# OLED.net
KiCad netlist of a schematic drawn in Altium Designer
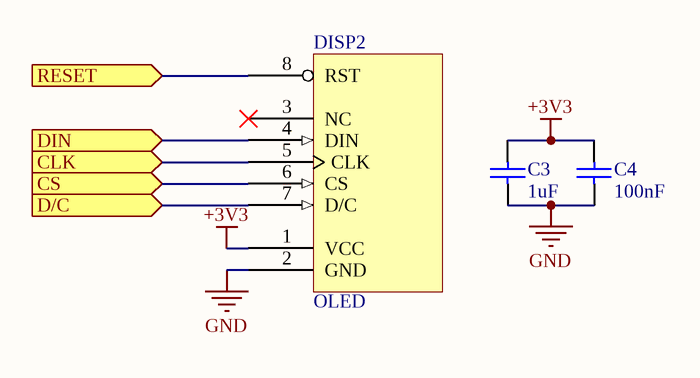
[diagram p0: OLED.SchDoc]

(export (version "E")
  (design (tool "Eeschema 10.0.6"))
  (components
    (comp (ref "C3")
      (value "1uF")
      (footprint "CAP_0805_IPC_MD")
      (description "Capacitor")
      (fields (field (name "MANUFACTURER") "Samsung") (field (name "Comment") "Cap"))
      (libsource (lib "DataLogger") (part "Cap"))
    )
    (comp (ref "C4")
      (value "100nF")
      (footprint "CAP_0805_IPC_MD")
      (description "Capacitor")
      (fields (field (name "MANUFACTURER") "Samsung") (field (name "Comment") "Cap"))
      (libsource (lib "DataLogger") (part "Cap"))
    )
    (comp (ref "DISP2")
      (value "OLED")
      (footprint "OLED_1.3_INCH")
      (libsource (lib "Dashboard") (part "OLED"))
    )
  )
  (nets
    (net (code "1") (name "+3V3") (class "Default")
      (node (ref "C3") (pin "2") (pinfunction "2_2") (pintype "passive"))
      (node (ref "C4") (pin "2") (pinfunction "2_2") (pintype "passive"))
      (node (ref "DISP2") (pin "1") (pinfunction "VCC_1") (pintype "power_in"))
    )
    (net (code "2") (name "/CLK") (class "Default")
      (node (ref "DISP2") (pin "5") (pinfunction "CLK_5") (pintype "passive"))
    )
    (net (code "3") (name "/CS") (class "Default")
      (node (ref "DISP2") (pin "6") (pinfunction "CS_6") (pintype "input"))
    )
    (net (code "4") (name "/DIN") (class "Default")
      (node (ref "DISP2") (pin "4") (pinfunction "DIN_4") (pintype "input"))
    )
    (net (code "5") (name "/D{slash}C") (class "Default")
      (node (ref "DISP2") (pin "7") (pinfunction "D/C_7") (pintype "input"))
    )
    (net (code "6") (name "/RESET") (class "Default")
      (node (ref "DISP2") (pin "8") (pinfunction "RST_8") (pintype "passive"))
    )
    (net (code "7") (name "GND") (class "Default")
      (node (ref "C3") (pin "1") (pinfunction "1_1") (pintype "passive"))
      (node (ref "C4") (pin "1") (pinfunction "1_1") (pintype "passive"))
      (node (ref "DISP2") (pin "2") (pinfunction "GND_2") (pintype "power_in"))
    )
    (net (code "8") (name "unconnected-(DISP2-NC-Pad3)") (class "Default")
      (node (ref "DISP2") (pin "3") (pinfunction "NC_3") (pintype "passive+no_connect"))
    )
  )
)
